# LPCB223_-_1_WIRE_DRIVER.net
KiCad netlist of a schematic drawn in Altium Designer
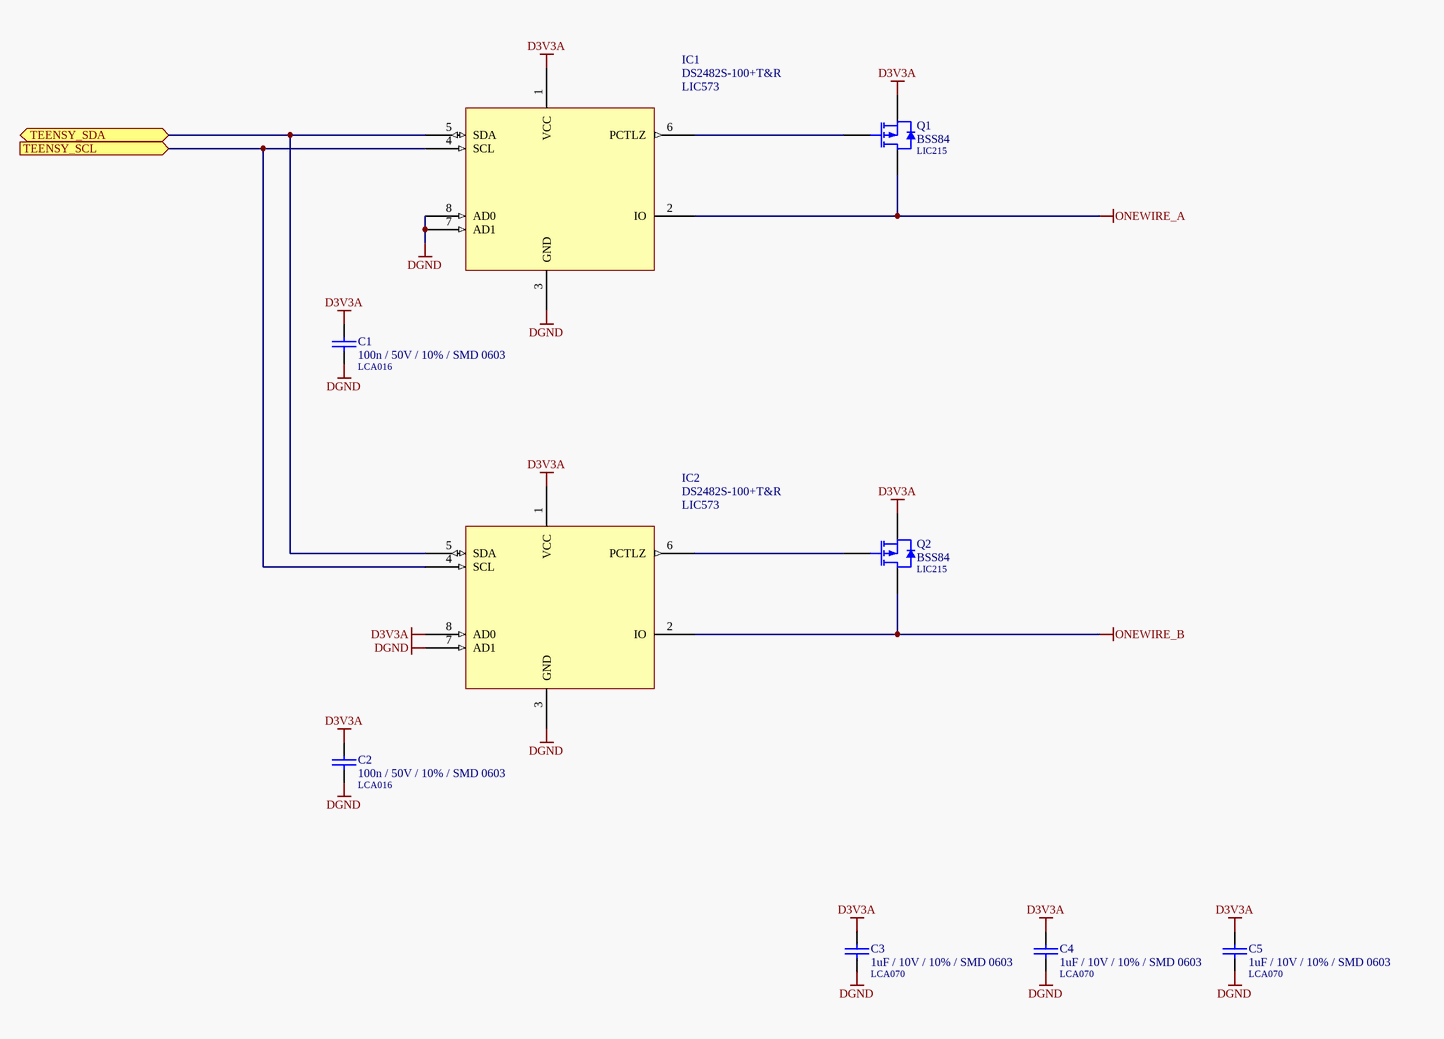
[diagram p0: LPCB223 - 1 WIRE DRIVER.SchDoc]

(export (version "E")
  (design (tool "Eeschema 10.0.6"))
  (components
    (comp (ref "C1")
      (value "100n / 50V / 10% / SMD 0603")
      (footprint "LFP011__CC1608-0603-IPC7351_B")
      (description "Capacitor, Ceramic Chip, 100nF (0.1uF), 50V, 5%, SMD 0603 [LCA016]")
      (fields (field (name "LDL_NUMBER") "LCA016"))
      (libsource (lib "LDL_Capacitors") (part "100n / 50V / 10% / SMD 0603"))
    )
    (comp (ref "C2")
      (value "100n / 50V / 10% / SMD 0603")
      (footprint "LFP011__CC1608-0603-IPC7351_B")
      (description "Capacitor, Ceramic Chip, 100nF (0.1uF), 50V, 5%, SMD 0603 [LCA016]")
      (fields (field (name "LDL_NUMBER") "LCA016"))
      (libsource (lib "LDL_Capacitors") (part "100n / 50V / 10% / SMD 0603"))
    )
    (comp (ref "C3")
      (value "1uF / 10V / 10% / SMD 0603")
      (footprint "LFP011__CC1608-0603-IPC7351_B")
      (description "Capacitor, Ceramic Chip, 1uF, 10V, SMD 0603 [LCA070]")
      (fields (field (name "LDL_NUMBER") "LCA070"))
      (libsource (lib "LDL_Capacitors") (part "1uF / 10V / 10% / SMD 0603"))
    )
    (comp (ref "C4")
      (value "1uF / 10V / 10% / SMD 0603")
      (footprint "LFP011__CC1608-0603-IPC7351_B")
      (description "Capacitor, Ceramic Chip, 1uF, 10V, SMD 0603 [LCA070]")
      (fields (field (name "LDL_NUMBER") "LCA070"))
      (libsource (lib "LDL_Capacitors") (part "1uF / 10V / 10% / SMD 0603"))
    )
    (comp (ref "C5")
      (value "1uF / 10V / 10% / SMD 0603")
      (footprint "LFP011__CC1608-0603-IPC7351_B")
      (description "Capacitor, Ceramic Chip, 1uF, 10V, SMD 0603 [LCA070]")
      (fields (field (name "LDL_NUMBER") "LCA070"))
      (libsource (lib "LDL_Capacitors") (part "1uF / 10V / 10% / SMD 0603"))
    )
    (comp (ref "IC1")
      (value "DS2482S-100+T&R")
      (footprint "LFP069__R-8G")
      (description "IC, I2C to 1 Wire Bridge, SMD SOIC8")
      (fields (field (name "LDL_NUMBER") "LIC573"))
      (libsource (lib "LDL_Semiconductors") (part "DS2482S-100+T&R"))
    )
    (comp (ref "IC2")
      (value "DS2482S-100+T&R")
      (footprint "LFP069__R-8G")
      (description "IC, I2C to 1 Wire Bridge, SMD SOIC8")
      (fields (field (name "LDL_NUMBER") "LIC573"))
      (libsource (lib "LDL_Semiconductors") (part "DS2482S-100+T&R"))
    )
    (comp (ref "Q1")
      (value "BSS84")
      (footprint "LFP021__SOT23")
      (description "FET, P Channel, Logic Level, SMD SOT23 [LIC215]")
      (fields (field (name "LDL_NUMBER") "LIC215"))
      (libsource (lib "LDL_Semiconductors") (part "BSS84"))
    )
    (comp (ref "Q2")
      (value "BSS84")
      (footprint "LFP021__SOT23")
      (description "FET, P Channel, Logic Level, SMD SOT23 [LIC215]")
      (fields (field (name "LDL_NUMBER") "LIC215"))
      (libsource (lib "LDL_Semiconductors") (part "BSS84"))
    )
  )
  (nets
    (net (code "1") (name "/TEENSY_SCL") (class "Default")
      (node (ref "IC1") (pin "4") (pinfunction "SCL_4") (pintype "input"))
      (node (ref "IC2") (pin "4") (pinfunction "SCL_4") (pintype "input"))
    )
    (net (code "2") (name "/TEENSY_SDA") (class "Default")
      (node (ref "IC1") (pin "5") (pinfunction "SDA_5") (pintype "bidirectional"))
      (node (ref "IC2") (pin "5") (pinfunction "SDA_5") (pintype "bidirectional"))
    )
    (net (code "3") (name "D3V3A") (class "Default")
      (node (ref "C1") (pin "1") (pintype "passive"))
      (node (ref "C2") (pin "1") (pintype "passive"))
      (node (ref "C3") (pin "1") (pintype "passive"))
      (node (ref "C4") (pin "1") (pintype "passive"))
      (node (ref "C5") (pin "1") (pintype "passive"))
      (node (ref "IC1") (pin "1") (pinfunction "VCC_1") (pintype "power_in"))
      (node (ref "IC2") (pin "1") (pinfunction "VCC_1") (pintype "power_in"))
      (node (ref "IC2") (pin "8") (pinfunction "AD0_8") (pintype "input"))
      (node (ref "Q1") (pin "2") (pinfunction "S_2") (pintype "passive"))
      (node (ref "Q2") (pin "2") (pinfunction "S_2") (pintype "passive"))
    )
    (net (code "4") (name "DGND") (class "Default")
      (node (ref "C1") (pin "2") (pintype "passive"))
      (node (ref "C2") (pin "2") (pintype "passive"))
      (node (ref "C3") (pin "2") (pintype "passive"))
      (node (ref "C4") (pin "2") (pintype "passive"))
      (node (ref "C5") (pin "2") (pintype "passive"))
      (node (ref "IC1") (pin "3") (pinfunction "GND_3") (pintype "power_in"))
      (node (ref "IC1") (pin "7") (pinfunction "AD1_7") (pintype "input"))
      (node (ref "IC1") (pin "8") (pinfunction "AD0_8") (pintype "input"))
      (node (ref "IC2") (pin "3") (pinfunction "GND_3") (pintype "power_in"))
      (node (ref "IC2") (pin "7") (pinfunction "AD1_7") (pintype "input"))
    )
    (net (code "5") (name "Net-(IC1-PCTLZ)") (class "Default")
      (node (ref "IC1") (pin "6") (pinfunction "PCTLZ_6") (pintype "output"))
      (node (ref "Q1") (pin "1") (pinfunction "G_1") (pintype "passive"))
    )
    (net (code "6") (name "Net-(IC2-PCTLZ)") (class "Default")
      (node (ref "IC2") (pin "6") (pinfunction "PCTLZ_6") (pintype "output"))
      (node (ref "Q2") (pin "1") (pinfunction "G_1") (pintype "passive"))
    )
    (net (code "7") (name "ONEWIRE_A") (class "Default")
      (node (ref "IC1") (pin "2") (pinfunction "IO_2") (pintype "passive"))
      (node (ref "Q1") (pin "3") (pinfunction "D_3") (pintype "passive"))
    )
    (net (code "8") (name "ONEWIRE_B") (class "Default")
      (node (ref "IC2") (pin "2") (pinfunction "IO_2") (pintype "passive"))
      (node (ref "Q2") (pin "3") (pinfunction "D_3") (pintype "passive"))
    )
  )
)
